# mcu.net
KiCad netlist of a schematic drawn in Altium Designer
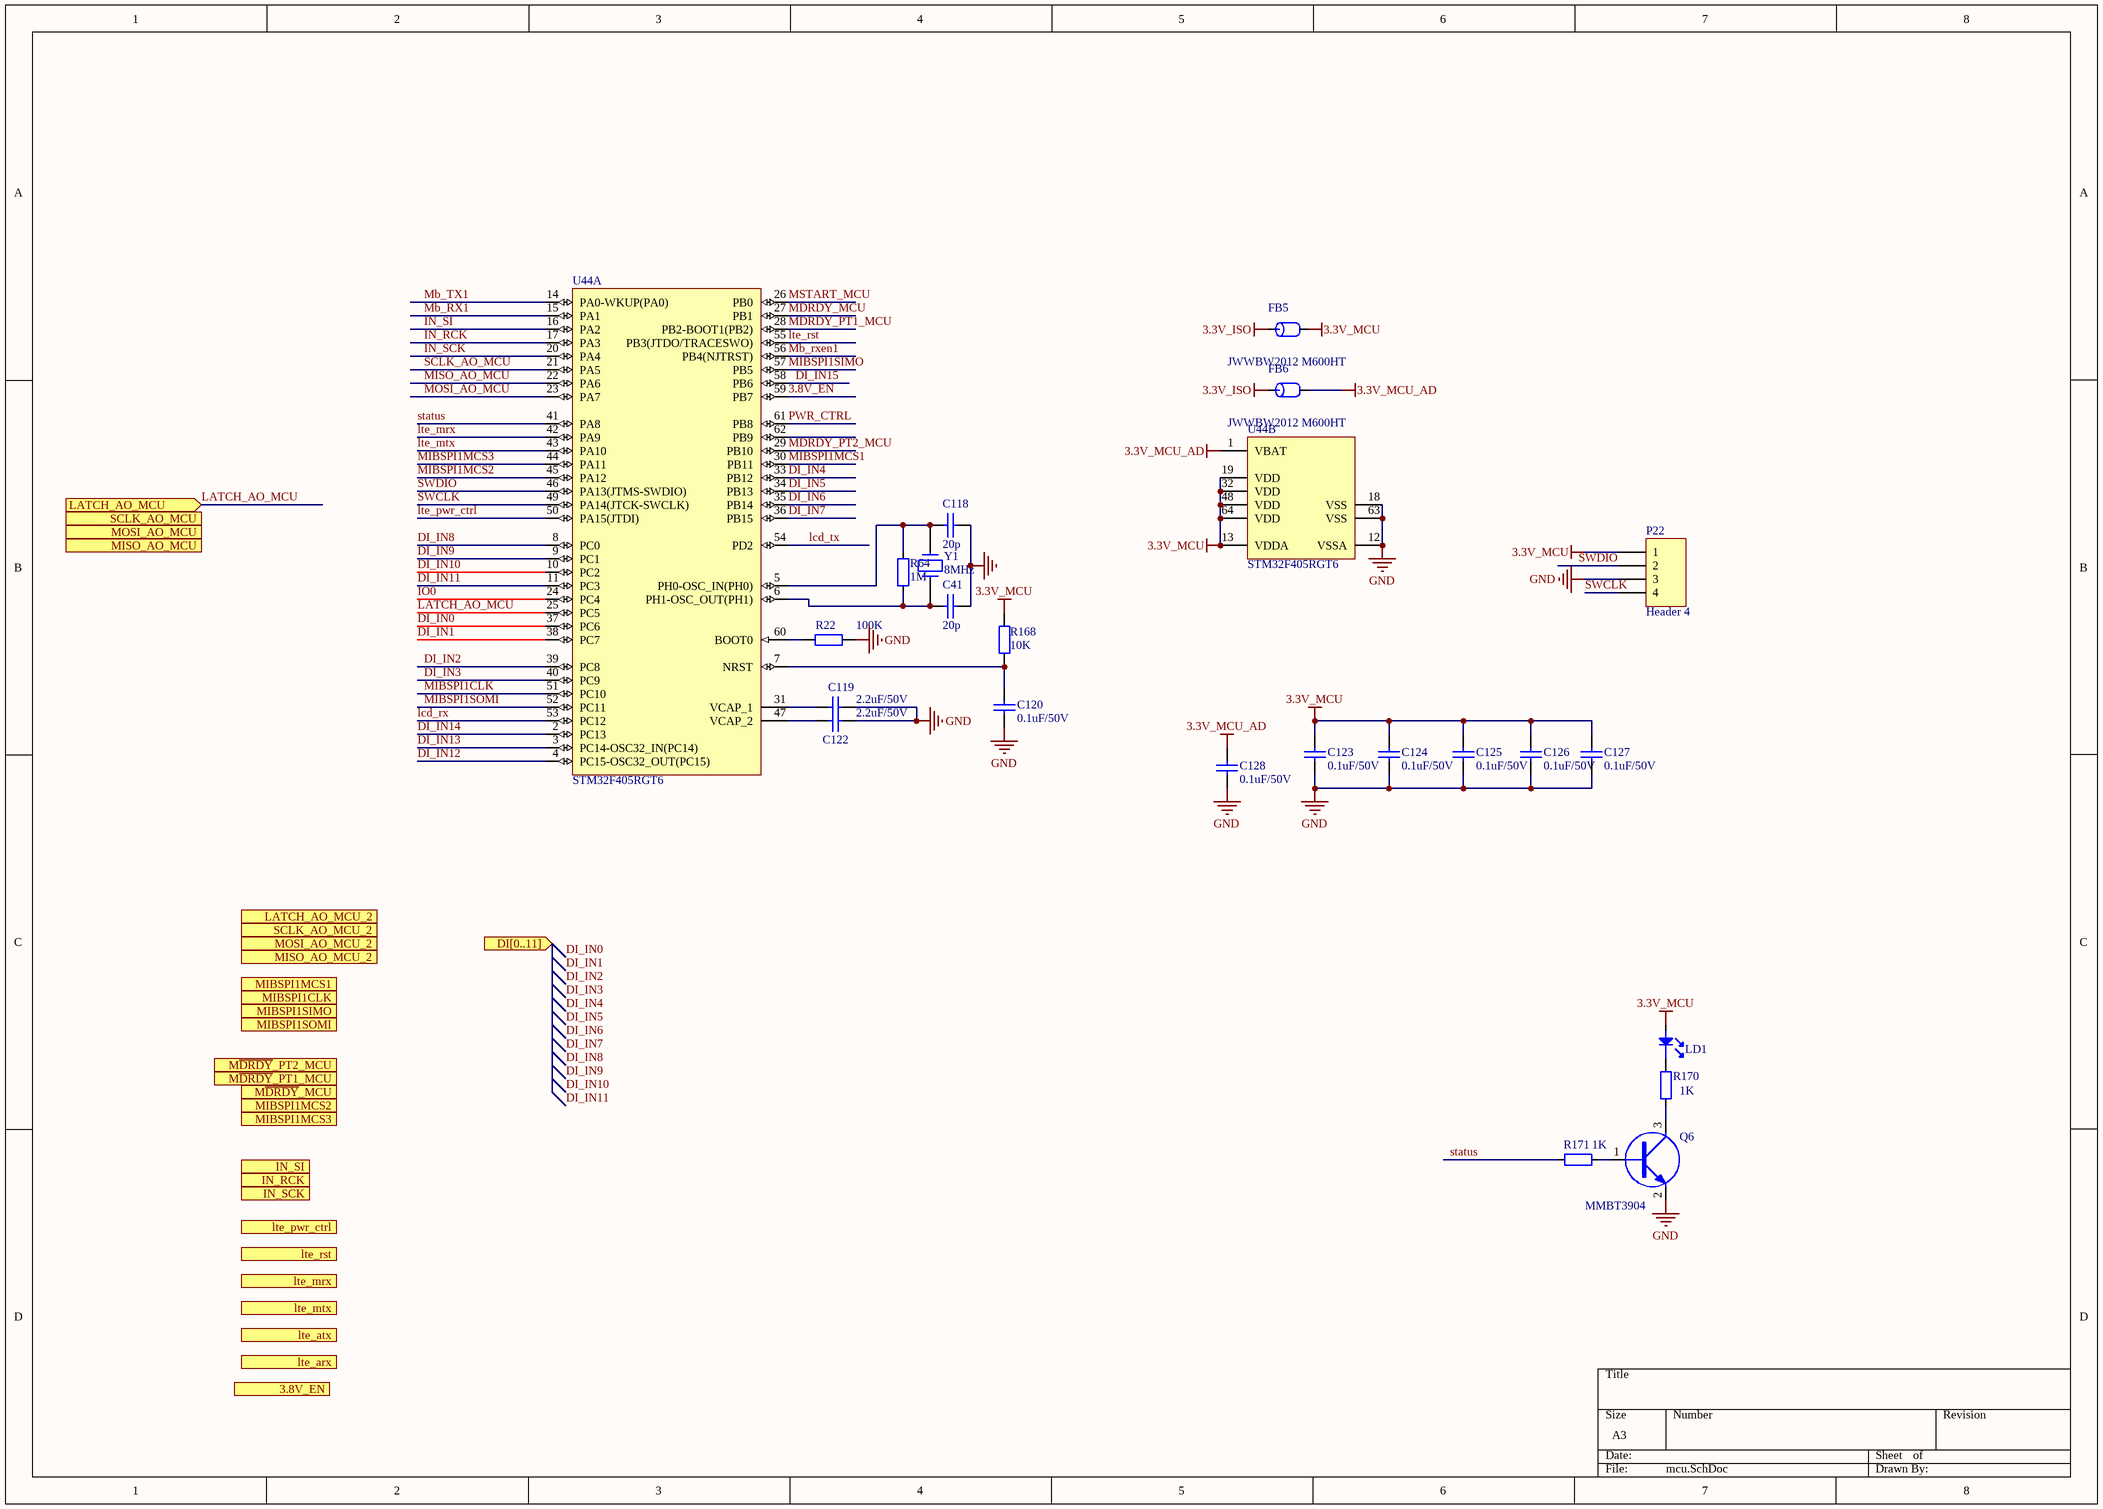
[diagram p0: mcu.SchDoc]

(export (version "E")
  (design (tool "Eeschema 10.0.6"))
  (components
    (comp (ref "C41")
      (value "20p")
      (footprint "0603c")
      (description "Capacitor")
      (libsource (lib "Schlib") (part "CAP"))
    )
    (comp (ref "C118")
      (value "20p")
      (footprint "0603c")
      (description "Capacitor")
      (libsource (lib "Schlib") (part "CAP"))
    )
    (comp (ref "C119")
      (value "2.2uF/50V")
      (footprint "0603C")
      (description "Capacitor")
      (fields (field (name "PUBLISHER") "Altium Limited"))
      (libsource (lib "Miscellaneous Devices") (part "Cap"))
    )
    (comp (ref "C120")
      (value "0.1uF/50V")
      (footprint "0603C")
      (description "Capacitor")
      (fields (field (name "PUBLISHER") "Altium Limited"))
      (libsource (lib "Miscellaneous Devices") (part "Cap"))
    )
    (comp (ref "C122")
      (value "2.2uF/50V")
      (footprint "0603C")
      (description "Capacitor")
      (fields (field (name "PUBLISHER") "Altium Limited"))
      (libsource (lib "Miscellaneous Devices") (part "Cap"))
    )
    (comp (ref "C123")
      (value "0.1uF/50V")
      (footprint "0603C")
      (description "Capacitor")
      (fields (field (name "PUBLISHER") "Altium Limited"))
      (libsource (lib "Miscellaneous Devices") (part "Cap"))
    )
    (comp (ref "C124")
      (value "0.1uF/50V")
      (footprint "0603C")
      (description "Capacitor")
      (fields (field (name "PUBLISHER") "Altium Limited"))
      (libsource (lib "Miscellaneous Devices") (part "Cap"))
    )
    (comp (ref "C125")
      (value "0.1uF/50V")
      (footprint "0603C")
      (description "Capacitor")
      (fields (field (name "PUBLISHER") "Altium Limited"))
      (libsource (lib "Miscellaneous Devices") (part "Cap"))
    )
    (comp (ref "C126")
      (value "0.1uF/50V")
      (footprint "0603C")
      (description "Capacitor")
      (fields (field (name "PUBLISHER") "Altium Limited"))
      (libsource (lib "Miscellaneous Devices") (part "Cap"))
    )
    (comp (ref "C127")
      (value "0.1uF/50V")
      (footprint "0603C")
      (description "Capacitor")
      (fields (field (name "PUBLISHER") "Altium Limited"))
      (libsource (lib "Miscellaneous Devices") (part "Cap"))
    )
    (comp (ref "C128")
      (value "0.1uF/50V")
      (footprint "0603C")
      (description "Capacitor")
      (fields (field (name "PUBLISHER") "Altium Limited"))
      (libsource (lib "Miscellaneous Devices") (part "Cap"))
    )
    (comp (ref "FB5")
      (value "JWWBW2012 M600HT")
      (footprint "0805R")
      (libsource (lib "Schlib_20110825") (part "FB"))
    )
    (comp (ref "FB6")
      (value "JWWBW2012 M600HT")
      (footprint "0805R")
      (libsource (lib "Schlib_20110825") (part "FB"))
    )
    (comp (ref "LD1")
      (value "LED_Green_19-217")
      (footprint "0603led")
      (libsource (lib "RC_M_D_00") (part "LED_Green_19-217"))
    )
    (comp (ref "P22")
      (value "Header 4")
      (footprint "HDR1X4")
      (description "Header, 4-Pin")
      (fields (field (name "PUBLISHER") "Altium Limited"))
      (libsource (lib "Miscellaneous Connectors") (part "Header 4"))
    )
    (comp (ref "Q6")
      (value "MMBT3904")
      (footprint "SOT23-3")
      (libsource (lib "CenLib") (part "NPN_MMBT3904"))
    )
    (comp (ref "R22") (value "100K") (footprint "0603R") (libsource (lib "MQlibrary") (part "Res0805M")))
    (comp (ref "R64") (value "1M") (footprint "0603R") (libsource (lib "RC_M_D_00") (part "RES0603")))
    (comp (ref "R168") (value "10K") (footprint "0603R") (libsource (lib "") (part "Res0805M_1")))
    (comp (ref "R170") (value "1K") (footprint "0603r") (libsource (lib "RC_M_D_00") (part "RES0603")))
    (comp (ref "R171") (value "1K") (footprint "0603r") (libsource (lib "RC_M_D_00") (part "RES0603")))
    (comp (ref "U44")
      (value "STM32F405RGT6")
      (footprint "LQFP-64")
      (fields (field (name "MANUFACTURER") "STMicroelectronics"))
      (libsource (lib "STMicroelectronics STM32 F4") (part "STM32F405RGT6"))
    )
    (comp (ref "Y1")
      (value "8MHz")
      (footprint "CRAY_5032")
      (description "HC49S-8MHz")
      (libsource (lib "*") (part "CRYSTAL"))
    )
  )
  (nets
    (net (code "13") (name "/3.8V_EN") (class "Default")
      (node (ref "U44") (pin "59") (pinfunction "PB7_59") (pintype "bidirectional"))
    )
    (net (code "15") (name "/DI_IN0") (class "Default")
      (node (ref "U44") (pin "37") (pinfunction "PC6_37") (pintype "bidirectional"))
    )
    (net (code "16") (name "/DI_IN1") (class "Default")
      (node (ref "U44") (pin "38") (pinfunction "PC7_38") (pintype "bidirectional"))
    )
    (net (code "17") (name "/DI_IN2") (class "Default")
      (node (ref "U44") (pin "39") (pinfunction "PC8_39") (pintype "bidirectional"))
    )
    (net (code "18") (name "/DI_IN3") (class "Default")
      (node (ref "U44") (pin "40") (pinfunction "PC9_40") (pintype "bidirectional"))
    )
    (net (code "19") (name "/DI_IN4") (class "Default")
      (node (ref "U44") (pin "33") (pinfunction "PB12_33") (pintype "bidirectional"))
    )
    (net (code "20") (name "/DI_IN5") (class "Default")
      (node (ref "U44") (pin "34") (pinfunction "PB13_34") (pintype "bidirectional"))
    )
    (net (code "21") (name "/DI_IN6") (class "Default")
      (node (ref "U44") (pin "35") (pinfunction "PB14_35") (pintype "bidirectional"))
    )
    (net (code "22") (name "/DI_IN7") (class "Default")
      (node (ref "U44") (pin "36") (pinfunction "PB15_36") (pintype "bidirectional"))
    )
    (net (code "23") (name "/DI_IN8") (class "Default")
      (node (ref "U44") (pin "8") (pinfunction "PC0_8") (pintype "bidirectional"))
    )
    (net (code "24") (name "/DI_IN9") (class "Default")
      (node (ref "U44") (pin "9") (pinfunction "PC1_9") (pintype "bidirectional"))
    )
    (net (code "25") (name "/DI_IN10") (class "Default")
      (node (ref "U44") (pin "10") (pinfunction "PC2_10") (pintype "bidirectional"))
    )
    (net (code "26") (name "/DI_IN11") (class "Default")
      (node (ref "U44") (pin "11") (pinfunction "PC3_11") (pintype "bidirectional"))
    )
    (net (code "27") (name "/DI_IN12") (class "Default")
      (node (ref "U44") (pin "4") (pinfunction "PC15-OSC32_OUT(PC15)_4") (pintype "bidirectional"))
    )
    (net (code "28") (name "/DI_IN13") (class "Default")
      (node (ref "U44") (pin "3") (pinfunction "PC14-OSC32_IN(PC14)_3") (pintype "bidirectional"))
    )
    (net (code "29") (name "/DI_IN14") (class "Default")
      (node (ref "U44") (pin "2") (pinfunction "PC13_2") (pintype "bidirectional"))
    )
    (net (code "30") (name "/DI_IN15") (class "Default")
      (node (ref "U44") (pin "58") (pinfunction "PB6_58") (pintype "bidirectional"))
    )
    (net (code "31") (name "/IN_RCK") (class "Default")
      (node (ref "U44") (pin "17") (pinfunction "PA3_17") (pintype "bidirectional"))
    )
    (net (code "32") (name "/IN_SCK") (class "Default")
      (node (ref "U44") (pin "20") (pinfunction "PA4_20") (pintype "bidirectional"))
    )
    (net (code "33") (name "/IN_SI") (class "Default")
      (node (ref "U44") (pin "16") (pinfunction "PA2_16") (pintype "bidirectional"))
    )
    (net (code "34") (name "/IO0") (class "Default")
      (node (ref "U44") (pin "24") (pinfunction "PC4_24") (pintype "bidirectional"))
    )
    (net (code "35") (name "/LATCH_AO_MCU") (class "Default")
      (node (ref "U44") (pin "25") (pinfunction "PC5_25") (pintype "bidirectional"))
    )
    (net (code "37") (name "/MIBSPI1CLK") (class "Default")
      (node (ref "U44") (pin "51") (pinfunction "PC10_51") (pintype "bidirectional"))
    )
    (net (code "38") (name "/MIBSPI1MCS1") (class "Default")
      (node (ref "U44") (pin "30") (pinfunction "PB11_30") (pintype "bidirectional"))
    )
    (net (code "39") (name "/MIBSPI1MCS2") (class "Default")
      (node (ref "U44") (pin "45") (pinfunction "PA12_45") (pintype "bidirectional"))
    )
    (net (code "40") (name "/MIBSPI1MCS3") (class "Default")
      (node (ref "U44") (pin "44") (pinfunction "PA11_44") (pintype "bidirectional"))
    )
    (net (code "41") (name "/MIBSPI1SIMO") (class "Default")
      (node (ref "U44") (pin "57") (pinfunction "PB5_57") (pintype "bidirectional"))
    )
    (net (code "42") (name "/MIBSPI1SOMI") (class "Default")
      (node (ref "U44") (pin "52") (pinfunction "PC11_52") (pintype "bidirectional"))
    )
    (net (code "43") (name "/MISO_AO_MCU") (class "Default")
      (node (ref "U44") (pin "22") (pinfunction "PA6_22") (pintype "bidirectional"))
    )
    (net (code "45") (name "/MOSI_AO_MCU") (class "Default")
      (node (ref "U44") (pin "23") (pinfunction "PA7_23") (pintype "bidirectional"))
    )
    (net (code "47") (name "/MSTART_MCU") (class "Default")
      (node (ref "U44") (pin "26") (pinfunction "PB0_26") (pintype "bidirectional"))
    )
    (net (code "48") (name "/Mb_RX1") (class "Default")
      (node (ref "U44") (pin "15") (pinfunction "PA1_15") (pintype "bidirectional"))
    )
    (net (code "49") (name "/Mb_TX1") (class "Default")
      (node (ref "U44") (pin "14") (pinfunction "PA0-WKUP(PA0)_14") (pintype "bidirectional"))
    )
    (net (code "50") (name "/Mb_rxen1") (class "Default")
      (node (ref "U44") (pin "56") (pinfunction "PB4(NJTRST)_56") (pintype "bidirectional"))
    )
    (net (code "51") (name "/M~{DRDY}_MCU") (class "Default")
      (node (ref "U44") (pin "27") (pinfunction "PB1_27") (pintype "bidirectional"))
    )
    (net (code "52") (name "/M~{DRDY}_PT1_MCU") (class "Default")
      (node (ref "U44") (pin "28") (pinfunction "PB2-BOOT1(PB2)_28") (pintype "bidirectional"))
    )
    (net (code "53") (name "/M~{DRDY}_PT2_MCU") (class "Default")
      (node (ref "U44") (pin "29") (pinfunction "PB10_29") (pintype "bidirectional"))
    )
    (net (code "54") (name "/PWR_CTRL") (class "Default")
      (node (ref "U44") (pin "61") (pinfunction "PB8_61") (pintype "bidirectional"))
    )
    (net (code "55") (name "/SCLK_AO_MCU") (class "Default")
      (node (ref "U44") (pin "21") (pinfunction "PA5_21") (pintype "bidirectional"))
    )
    (net (code "57") (name "/SWCLK") (class "Default")
      (node (ref "P22") (pin "4") (pinfunction "4_4") (pintype "passive"))
      (node (ref "U44") (pin "49") (pinfunction "PA14(JTCK-SWCLK)_49") (pintype "bidirectional"))
    )
    (net (code "58") (name "/SWDIO") (class "Default")
      (node (ref "P22") (pin "2") (pinfunction "2_2") (pintype "passive"))
      (node (ref "U44") (pin "46") (pinfunction "PA13(JTMS-SWDIO)_46") (pintype "bidirectional"))
    )
    (net (code "59") (name "/lcd_rx") (class "Default")
      (node (ref "U44") (pin "53") (pinfunction "PC12_53") (pintype "bidirectional"))
    )
    (net (code "60") (name "/lcd_tx") (class "Default")
      (node (ref "U44") (pin "54") (pinfunction "PD2_54") (pintype "bidirectional"))
    )
    (net (code "63") (name "/lte_mrx") (class "Default")
      (node (ref "U44") (pin "42") (pinfunction "PA9_42") (pintype "bidirectional"))
    )
    (net (code "64") (name "/lte_mtx") (class "Default")
      (node (ref "U44") (pin "43") (pinfunction "PA10_43") (pintype "bidirectional"))
    )
    (net (code "65") (name "/lte_pwr_ctrl") (class "Default")
      (node (ref "U44") (pin "50") (pinfunction "PA15(JTDI)_50") (pintype "bidirectional"))
    )
    (net (code "66") (name "/lte_rst") (class "Default")
      (node (ref "U44") (pin "55") (pinfunction "PB3(JTDO/TRACESWO)_55") (pintype "bidirectional"))
    )
    (net (code "67") (name "/status") (class "Default")
      (node (ref "R171") (pin "1") (pinfunction "1_1") (pintype "passive"))
      (node (ref "U44") (pin "41") (pinfunction "PA8_41") (pintype "bidirectional"))
    )
    (net (code "68") (name "3.3V_ISO") (class "Default")
      (node (ref "FB5") (pin "1") (pintype "passive"))
      (node (ref "FB6") (pin "1") (pintype "passive"))
    )
    (net (code "69") (name "3.3V_MCU") (class "Default")
      (node (ref "C123") (pin "2") (pinfunction "2_2") (pintype "passive"))
      (node (ref "C124") (pin "2") (pinfunction "2_2") (pintype "passive"))
      (node (ref "C125") (pin "2") (pinfunction "2_2") (pintype "passive"))
      (node (ref "C126") (pin "2") (pinfunction "2_2") (pintype "passive"))
      (node (ref "C127") (pin "2") (pinfunction "2_2") (pintype "passive"))
      (node (ref "FB5") (pin "2") (pintype "passive"))
      (node (ref "LD1") (pin "1") (pinfunction "1_1") (pintype "passive"))
      (node (ref "P22") (pin "1") (pinfunction "1_1") (pintype "passive"))
      (node (ref "R168") (pin "2") (pinfunction "2_2") (pintype "passive"))
      (node (ref "U44") (pin "13") (pinfunction "VDDA_13") (pintype "power_in"))
      (node (ref "U44") (pin "19") (pinfunction "VDD_19") (pintype "power_in"))
      (node (ref "U44") (pin "32") (pinfunction "VDD_32") (pintype "power_in"))
      (node (ref "U44") (pin "48") (pinfunction "VDD_48") (pintype "power_in"))
      (node (ref "U44") (pin "64") (pinfunction "VDD_64") (pintype "power_in"))
    )
    (net (code "70") (name "3.3V_MCU_AD") (class "Default")
      (node (ref "C128") (pin "2") (pinfunction "2_2") (pintype "passive"))
      (node (ref "FB6") (pin "2") (pintype "passive"))
      (node (ref "U44") (pin "1") (pinfunction "VBAT_1") (pintype "power_in"))
    )
    (net (code "71") (name "GND") (class "Default")
      (node (ref "C118") (pin "1") (pinfunction "1_1") (pintype "passive"))
      (node (ref "C119") (pin "1") (pinfunction "1_1") (pintype "passive"))
      (node (ref "C120") (pin "1") (pinfunction "1_1") (pintype "passive"))
      (node (ref "C122") (pin "1") (pinfunction "1_1") (pintype "passive"))
      (node (ref "C123") (pin "1") (pinfunction "1_1") (pintype "passive"))
      (node (ref "C124") (pin "1") (pinfunction "1_1") (pintype "passive"))
      (node (ref "C125") (pin "1") (pinfunction "1_1") (pintype "passive"))
      (node (ref "C126") (pin "1") (pinfunction "1_1") (pintype "passive"))
      (node (ref "C127") (pin "1") (pinfunction "1_1") (pintype "passive"))
      (node (ref "C128") (pin "1") (pinfunction "1_1") (pintype "passive"))
      (node (ref "C41") (pin "1") (pinfunction "1_1") (pintype "passive"))
      (node (ref "P22") (pin "3") (pinfunction "3_3") (pintype "passive"))
      (node (ref "Q6") (pin "2") (pinfunction "E_2") (pintype "passive"))
      (node (ref "R22") (pin "2") (pinfunction "2_2") (pintype "passive"))
      (node (ref "U44") (pin "12") (pinfunction "VSSA_12") (pintype "power_in"))
      (node (ref "U44") (pin "18") (pinfunction "VSS_18") (pintype "power_in"))
      (node (ref "U44") (pin "63") (pinfunction "VSS_63") (pintype "power_in"))
    )
    (net (code "72") (name "Net-(LD1-Pad2)") (class "Default")
      (node (ref "LD1") (pin "2") (pinfunction "2_2") (pintype "passive"))
      (node (ref "R170") (pin "1") (pinfunction "1_1") (pintype "passive"))
    )
    (net (code "73") (name "Net-(Q6-B)") (class "Default")
      (node (ref "Q6") (pin "1") (pinfunction "B_1") (pintype "passive"))
      (node (ref "R171") (pin "2") (pinfunction "2_2") (pintype "passive"))
    )
    (net (code "74") (name "Net-(Q6-C)") (class "Default")
      (node (ref "Q6") (pin "3") (pinfunction "C_3") (pintype "passive"))
      (node (ref "R170") (pin "2") (pinfunction "2_2") (pintype "passive"))
    )
    (net (code "75") (name "Net-(U44A-BOOT0)") (class "Default")
      (node (ref "R22") (pin "1") (pinfunction "1_1") (pintype "passive"))
      (node (ref "U44") (pin "60") (pinfunction "BOOT0_60") (pintype "input"))
    )
    (net (code "76") (name "Net-(U44A-NRST)") (class "Default")
      (node (ref "C120") (pin "2") (pinfunction "2_2") (pintype "passive"))
      (node (ref "R168") (pin "1") (pinfunction "1_1") (pintype "passive"))
      (node (ref "U44") (pin "7") (pinfunction "NRST_7") (pintype "bidirectional"))
    )
    (net (code "77") (name "Net-(U44A-PH0-OSC_IN(PH0))") (class "Default")
      (node (ref "C118") (pin "2") (pinfunction "2_2") (pintype "passive"))
      (node (ref "R64") (pin "2") (pinfunction "2_2") (pintype "passive"))
      (node (ref "U44") (pin "5") (pinfunction "PH0-OSC_IN(PH0)_5") (pintype "bidirectional"))
      (node (ref "Y1") (pin "1") (pinfunction "1_1") (pintype "passive"))
    )
    (net (code "78") (name "Net-(U44A-PH1-OSC_OUT(PH1))") (class "Default")
      (node (ref "C41") (pin "2") (pinfunction "2_2") (pintype "passive"))
      (node (ref "R64") (pin "1") (pinfunction "1_1") (pintype "passive"))
      (node (ref "U44") (pin "6") (pinfunction "PH1-OSC_OUT(PH1)_6") (pintype "bidirectional"))
      (node (ref "Y1") (pin "2") (pinfunction "2_2") (pintype "passive"))
    )
    (net (code "79") (name "Net-(U44A-VCAP_1)") (class "Default")
      (node (ref "C119") (pin "2") (pinfunction "2_2") (pintype "passive"))
      (node (ref "U44") (pin "31") (pinfunction "VCAP_1_31") (pintype "power_in"))
    )
    (net (code "80") (name "Net-(U44A-VCAP_2)") (class "Default")
      (node (ref "C122") (pin "2") (pinfunction "2_2") (pintype "passive"))
      (node (ref "U44") (pin "47") (pinfunction "VCAP_2_47") (pintype "power_in"))
    )
    (net (code "81") (name "unconnected-(U44A-PB9-Pad62)") (class "Default")
      (node (ref "U44") (pin "62") (pinfunction "PB9_62") (pintype "bidirectional"))
    )
  )
)
